# Sheet1.net
KiCad netlist of a schematic drawn in Altium Designer
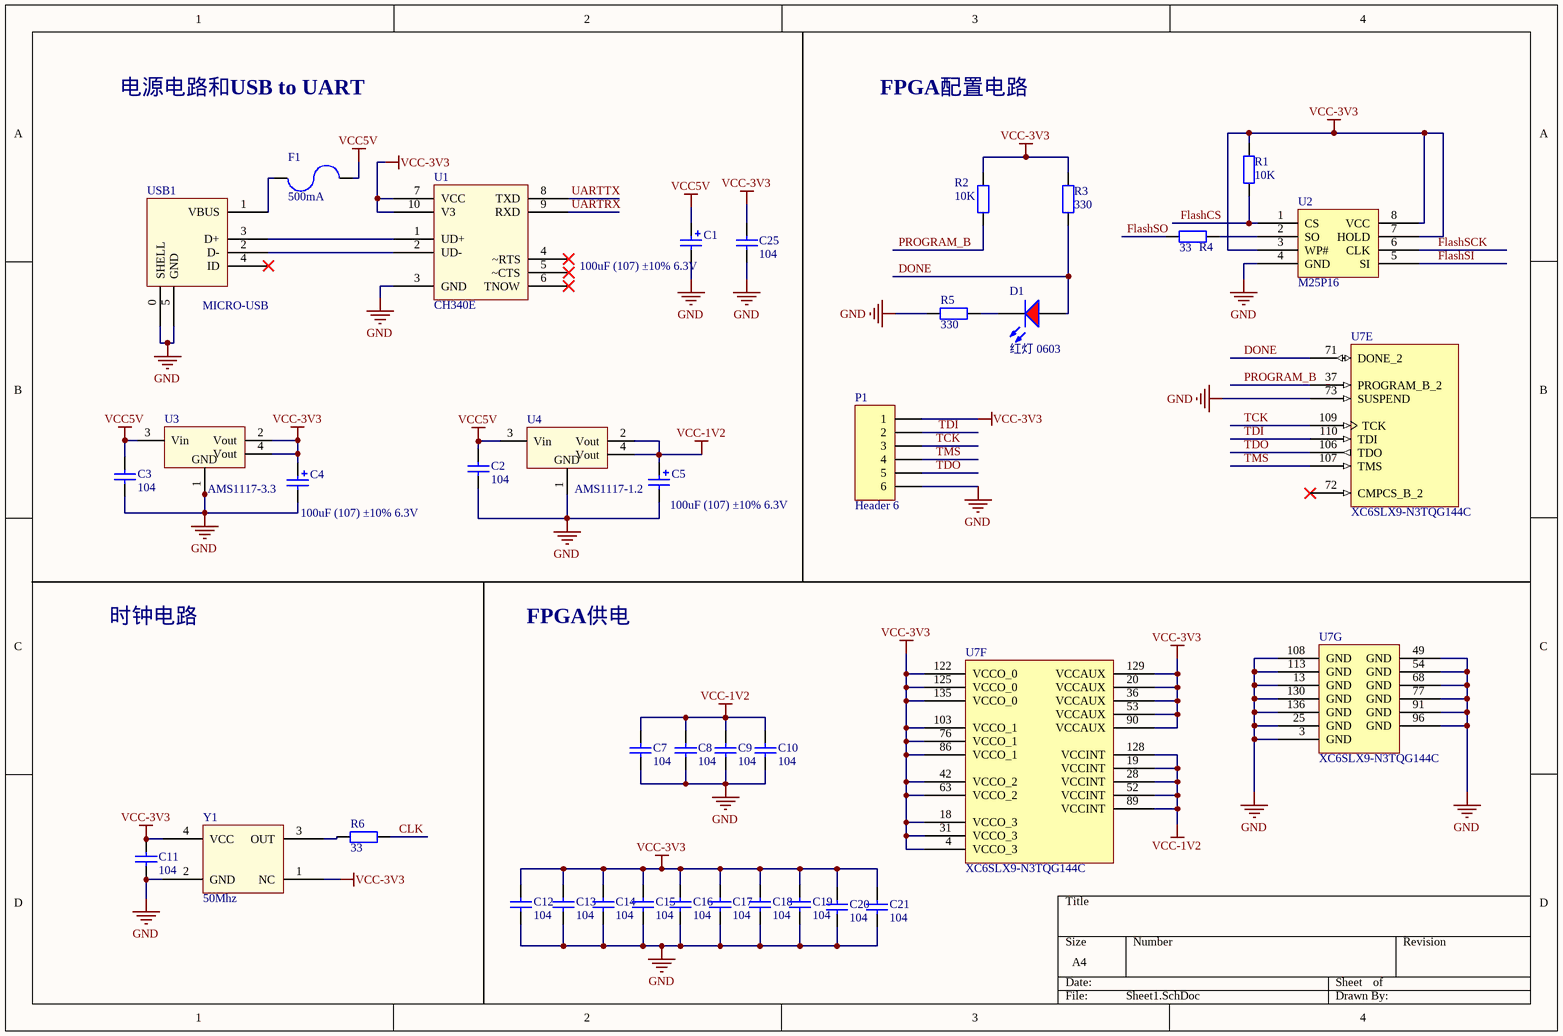
[diagram p0: Sheet1.SchDoc]

(export (version "E")
  (design (tool "Eeschema 10.0.6"))
  (components
    (comp (ref "C1")
      (value "100uF (107) ±10% 6.3V")
      (footprint "CASE-B_3528")
      (description "钽电容")
      (libsource (lib "Cap") (part "3528 100uF (107) 10% 6.3V"))
    )
    (comp (ref "C2")
      (value "104")
      (footprint "0603_C")
      (description "贴片电容")
      (libsource (lib "Cap") (part "0603 30pF (300) 5% 50V"))
    )
    (comp (ref "C3")
      (value "104")
      (footprint "0603_C")
      (description "贴片电容")
      (libsource (lib "Cap") (part "0603 30pF (300) 5% 50V"))
    )
    (comp (ref "C4")
      (value "100uF (107) ±10% 6.3V")
      (footprint "CASE-B_3528")
      (description "钽电容")
      (libsource (lib "Cap") (part "3528 100uF (107) 10% 6.3V"))
    )
    (comp (ref "C5")
      (value "100uF (107) ±10% 6.3V")
      (footprint "CASE-B_3528")
      (description "钽电容")
      (libsource (lib "Cap") (part "3528 100uF (107) 10% 6.3V"))
    )
    (comp (ref "C7")
      (value "104")
      (footprint "0603_C")
      (description "贴片电容")
      (libsource (lib "Cap") (part "0603 30pF (300) 5% 50V"))
    )
    (comp (ref "C8")
      (value "104")
      (footprint "0603_C")
      (description "贴片电容")
      (libsource (lib "Cap") (part "0603 30pF (300) 5% 50V"))
    )
    (comp (ref "C9")
      (value "104")
      (footprint "0603_C")
      (description "贴片电容")
      (libsource (lib "Cap") (part "0603 30pF (300) 5% 50V"))
    )
    (comp (ref "C10")
      (value "104")
      (footprint "0603_C")
      (description "贴片电容")
      (libsource (lib "Cap") (part "0603 30pF (300) 5% 50V"))
    )
    (comp (ref "C11")
      (value "104")
      (footprint "0603_C")
      (description "贴片电容")
      (libsource (lib "Cap") (part "0603 30pF (300) 5% 50V"))
    )
    (comp (ref "C12")
      (value "104")
      (footprint "0603_C")
      (description "贴片电容")
      (libsource (lib "Cap") (part "0603 30pF (300) 5% 50V"))
    )
    (comp (ref "C13")
      (value "104")
      (footprint "0603_C")
      (description "贴片电容")
      (libsource (lib "Cap") (part "0603 30pF (300) 5% 50V"))
    )
    (comp (ref "C14")
      (value "104")
      (footprint "0603_C")
      (description "贴片电容")
      (libsource (lib "Cap") (part "0603 30pF (300) 5% 50V"))
    )
    (comp (ref "C15")
      (value "104")
      (footprint "0603_C")
      (description "贴片电容")
      (libsource (lib "Cap") (part "0603 30pF (300) 5% 50V"))
    )
    (comp (ref "C16")
      (value "104")
      (footprint "0603_C")
      (description "贴片电容")
      (libsource (lib "Cap") (part "0603 30pF (300) 5% 50V"))
    )
    (comp (ref "C17")
      (value "104")
      (footprint "0603_C")
      (description "贴片电容")
      (libsource (lib "Cap") (part "0603 30pF (300) 5% 50V"))
    )
    (comp (ref "C18")
      (value "104")
      (footprint "0603_C")
      (description "贴片电容")
      (libsource (lib "Cap") (part "0603 30pF (300) 5% 50V"))
    )
    (comp (ref "C19")
      (value "104")
      (footprint "0603_C")
      (description "贴片电容")
      (libsource (lib "Cap") (part "0603 30pF (300) 5% 50V"))
    )
    (comp (ref "C20")
      (value "104")
      (footprint "0603_C")
      (description "贴片电容")
      (libsource (lib "Cap") (part "0603 30pF (300) 5% 50V"))
    )
    (comp (ref "C21")
      (value "104")
      (footprint "0603_C")
      (description "贴片电容")
      (libsource (lib "Cap") (part "0603 30pF (300) 5% 50V"))
    )
    (comp (ref "C25")
      (value "104")
      (footprint "0603_C")
      (description "贴片电容")
      (libsource (lib "Cap") (part "0603 30pF (300) 5% 50V"))
    )
    (comp (ref "D1")
      (value "红灯 0603")
      (footprint "0603_LED_S1")
      (description "发光二极管")
      (libsource (lib "LED") (part "0603 红灯"))
    )
    (comp (ref "F1") (value "500mA") (footprint "PTC[0805]") (libsource (lib "MiniSTM32") (part "PTC")))
    (comp (ref "P1")
      (value "Header 6")
      (footprint "HDR1X6")
      (description "Header, 6-Pin")
      (fields (field (name "PUBLISHER") "Altium Limited"))
      (libsource (lib "Miscellaneous Connectors") (part "Header 6"))
    )
    (comp (ref "R1")
      (value "10K")
      (footprint "0603_R")
      (description "贴片电阻")
      (libsource (lib "") (part "0603 9.1KΩ (9101) 1%_1"))
    )
    (comp (ref "R2")
      (value "10K")
      (footprint "0603_R")
      (description "贴片电阻")
      (libsource (lib "") (part "0603 9.1KΩ (9101) 1%_1"))
    )
    (comp (ref "R3")
      (value "330")
      (footprint "0603_R")
      (description "贴片电阻")
      (libsource (lib "") (part "0603 9.1KΩ (9101) 1%_1"))
    )
    (comp (ref "R4")
      (value "33")
      (footprint "0603_R")
      (description "贴片电阻")
      (libsource (lib "RES") (part "0603 9.1KΩ (9101) 1%"))
    )
    (comp (ref "R5")
      (value "330")
      (footprint "0603_R")
      (description "贴片电阻")
      (libsource (lib "RES") (part "0603 9.1KΩ (9101) 1%"))
    )
    (comp (ref "R6")
      (value "33")
      (footprint "0603_R")
      (description "贴片电阻")
      (libsource (lib "RES") (part "0603 9.1KΩ (9101) 1%"))
    )
    (comp (ref "U1") (value "CH340E") (footprint "MSOP10") (libsource (lib "MYDDS") (part "CH340E")))
    (comp (ref "U2") (value "M25P16") (footprint "SO-8") (libsource (lib "MiniSTM32") (part "W25Q64")))
    (comp (ref "U3")
      (value "AMS1117-3.3")
      (footprint "SOT-223(AMS1117-3.3)")
      (libsource (lib "MiniSTM32") (part "AMS1117-3.3"))
    )
    (comp (ref "U4")
      (value "AMS1117-1.2")
      (footprint "SOT-223(AMS1117-3.3)")
      (libsource (lib "MiniSTM32") (part "AMS1117-3.3"))
    )
    (comp (ref "U7")
      (value "XC6SLX9-N3TQG144C")
      (footprint "TQG144_N")
      (fields (field (name "PUBLISHER") "Altium Limited"))
      (libsource (lib "Xilinx Spartan-6") (part "XC6SLX9-N3TQG144C"))
    )
    (comp (ref "USB1")
      (value "MICRO-USB")
      (footprint "MICRO-USB")
      (libsource (lib "MYDDS") (part "MICRO-USB"))
    )
    (comp (ref "Y1") (value "50Mhz") (footprint "XTAL5032") (libsource (lib "MYSCH") (part "有源晶振")))
  )
  (nets
    (net (code "1") (name "/CLK") (class "Default")
      (node (ref "R6") (pin "1") (pinfunction "1_1") (pintype "passive"))
    )
    (net (code "2") (name "/DONE") (class "Default")
      (node (ref "D1") (pin "A") (pinfunction "A_A") (pintype "passive"))
      (node (ref "R3") (pin "1") (pinfunction "1_1") (pintype "passive"))
      (node (ref "U7") (pin "71") (pinfunction "DONE_2_71") (pintype "bidirectional"))
    )
    (net (code "3") (name "/FlashCS") (class "Default")
      (node (ref "R1") (pin "1") (pinfunction "1_1") (pintype "passive"))
      (node (ref "U2") (pin "1") (pinfunction "CS_1") (pintype "passive"))
    )
    (net (code "4") (name "/FlashSCK") (class "Default")
      (node (ref "U2") (pin "6") (pinfunction "CLK_6") (pintype "passive"))
    )
    (net (code "5") (name "/FlashSI") (class "Default")
      (node (ref "U2") (pin "5") (pinfunction "SI_5") (pintype "passive"))
    )
    (net (code "6") (name "/FlashSO") (class "Default")
      (node (ref "R4") (pin "2") (pinfunction "2_2") (pintype "passive"))
    )
    (net (code "7") (name "/PROGRAM_B") (class "Default")
      (node (ref "R2") (pin "1") (pinfunction "1_1") (pintype "passive"))
      (node (ref "U7") (pin "37") (pinfunction "PROGRAM_B_2_37") (pintype "input"))
    )
    (net (code "8") (name "/TCK") (class "Default")
      (node (ref "P1") (pin "3") (pinfunction "3_3") (pintype "passive"))
      (node (ref "U7") (pin "109") (pinfunction "TCK_109") (pintype "input"))
    )
    (net (code "9") (name "/TDI") (class "Default")
      (node (ref "P1") (pin "2") (pinfunction "2_2") (pintype "passive"))
      (node (ref "U7") (pin "110") (pinfunction "TDI_110") (pintype "input"))
    )
    (net (code "10") (name "/TDO") (class "Default")
      (node (ref "P1") (pin "5") (pinfunction "5_5") (pintype "passive"))
      (node (ref "U7") (pin "106") (pinfunction "TDO_106") (pintype "output"))
    )
    (net (code "11") (name "/TMS") (class "Default")
      (node (ref "P1") (pin "4") (pinfunction "4_4") (pintype "passive"))
      (node (ref "U7") (pin "107") (pinfunction "TMS_107") (pintype "input"))
    )
    (net (code "12") (name "/UARTRX") (class "Default")
      (node (ref "U1") (pin "9") (pinfunction "RXD_9") (pintype "passive"))
    )
    (net (code "13") (name "/UARTTX") (class "Default")
      (node (ref "U1") (pin "8") (pinfunction "TXD_8") (pintype "passive"))
    )
    (net (code "14") (name "GND") (class "Default")
      (node (ref "C1") (pin "2") (pinfunction "2_2") (pintype "passive"))
      (node (ref "C10") (pin "1") (pinfunction "1_1") (pintype "passive"))
      (node (ref "C11") (pin "1") (pinfunction "1_1") (pintype "passive"))
      (node (ref "C12") (pin "1") (pinfunction "1_1") (pintype "passive"))
      (node (ref "C13") (pin "1") (pinfunction "1_1") (pintype "passive"))
      (node (ref "C14") (pin "1") (pinfunction "1_1") (pintype "passive"))
      (node (ref "C15") (pin "1") (pinfunction "1_1") (pintype "passive"))
      (node (ref "C16") (pin "1") (pinfunction "1_1") (pintype "passive"))
      (node (ref "C17") (pin "1") (pinfunction "1_1") (pintype "passive"))
      (node (ref "C18") (pin "1") (pinfunction "1_1") (pintype "passive"))
      (node (ref "C19") (pin "1") (pinfunction "1_1") (pintype "passive"))
      (node (ref "C2") (pin "1") (pinfunction "1_1") (pintype "passive"))
      (node (ref "C20") (pin "1") (pinfunction "1_1") (pintype "passive"))
      (node (ref "C21") (pin "1") (pinfunction "1_1") (pintype "passive"))
      (node (ref "C25") (pin "1") (pinfunction "1_1") (pintype "passive"))
      (node (ref "C3") (pin "1") (pinfunction "1_1") (pintype "passive"))
      (node (ref "C4") (pin "2") (pinfunction "2_2") (pintype "passive"))
      (node (ref "C5") (pin "2") (pinfunction "2_2") (pintype "passive"))
      (node (ref "C7") (pin "1") (pinfunction "1_1") (pintype "passive"))
      (node (ref "C8") (pin "1") (pinfunction "1_1") (pintype "passive"))
      (node (ref "C9") (pin "1") (pinfunction "1_1") (pintype "passive"))
      (node (ref "P1") (pin "6") (pinfunction "6_6") (pintype "passive"))
      (node (ref "R5") (pin "2") (pinfunction "2_2") (pintype "passive"))
      (node (ref "U1") (pin "3") (pinfunction "GND_3") (pintype "passive"))
      (node (ref "U2") (pin "4") (pinfunction "GND_4") (pintype "passive"))
      (node (ref "U3") (pin "1") (pinfunction "GND_1") (pintype "passive"))
      (node (ref "U4") (pin "1") (pinfunction "GND_1") (pintype "passive"))
      (node (ref "U7") (pin "108") (pinfunction "GND_108") (pintype "power_in"))
      (node (ref "U7") (pin "113") (pinfunction "GND_113") (pintype "power_in"))
      (node (ref "U7") (pin "13") (pinfunction "GND_13") (pintype "power_in"))
      (node (ref "U7") (pin "130") (pinfunction "GND_130") (pintype "power_in"))
      (node (ref "U7") (pin "136") (pinfunction "GND_136") (pintype "power_in"))
      (node (ref "U7") (pin "25") (pinfunction "GND_25") (pintype "power_in"))
      (node (ref "U7") (pin "3") (pinfunction "GND_3") (pintype "power_in"))
      (node (ref "U7") (pin "49") (pinfunction "GND_49") (pintype "power_in"))
      (node (ref "U7") (pin "54") (pinfunction "GND_54") (pintype "power_in"))
      (node (ref "U7") (pin "68") (pinfunction "GND_68") (pintype "power_in"))
      (node (ref "U7") (pin "73") (pinfunction "SUSPEND_73") (pintype "input"))
      (node (ref "U7") (pin "77") (pinfunction "GND_77") (pintype "power_in"))
      (node (ref "U7") (pin "91") (pinfunction "GND_91") (pintype "power_in"))
      (node (ref "U7") (pin "96") (pinfunction "GND_96") (pintype "power_in"))
      (node (ref "USB1") (pin "0") (pinfunction "SHELL_0") (pintype "passive"))
      (node (ref "USB1") (pin "5") (pinfunction "GND_5") (pintype "passive"))
      (node (ref "Y1") (pin "2") (pinfunction "GND_2") (pintype "passive"))
    )
    (net (code "15") (name "Net-(D1-PadK)") (class "Default")
      (node (ref "D1") (pin "K") (pinfunction "K_K") (pintype "passive"))
      (node (ref "R5") (pin "1") (pinfunction "1_1") (pintype "passive"))
    )
    (net (code "16") (name "Net-(U1-UD+)") (class "Default")
      (node (ref "U1") (pin "1") (pinfunction "UD+_1") (pintype "passive"))
      (node (ref "USB1") (pin "3") (pinfunction "D+_3") (pintype "passive"))
    )
    (net (code "17") (name "Net-(U1-UD-)") (class "Default")
      (node (ref "U1") (pin "2") (pinfunction "UD-_2") (pintype "passive"))
      (node (ref "USB1") (pin "2") (pinfunction "D-_2") (pintype "passive"))
    )
    (net (code "18") (name "Net-(U2-SO)") (class "Default")
      (node (ref "R4") (pin "1") (pinfunction "1_1") (pintype "passive"))
      (node (ref "U2") (pin "2") (pinfunction "SO_2") (pintype "passive"))
    )
    (net (code "19") (name "Net-(USB1-VBUS)") (class "Default")
      (node (ref "F1") (pin "2") (pinfunction "2_2") (pintype "passive"))
      (node (ref "USB1") (pin "1") (pinfunction "VBUS_1") (pintype "passive"))
    )
    (net (code "20") (name "Net-(Y1-OUT)") (class "Default")
      (node (ref "R6") (pin "2") (pinfunction "2_2") (pintype "passive"))
      (node (ref "Y1") (pin "3") (pinfunction "OUT_3") (pintype "passive"))
    )
    (net (code "21") (name "VCC-1V2") (class "Default")
      (node (ref "C10") (pin "2") (pinfunction "2_2") (pintype "passive"))
      (node (ref "C5") (pin "1") (pinfunction "1_1") (pintype "passive"))
      (node (ref "C7") (pin "2") (pinfunction "2_2") (pintype "passive"))
      (node (ref "C8") (pin "2") (pinfunction "2_2") (pintype "passive"))
      (node (ref "C9") (pin "2") (pinfunction "2_2") (pintype "passive"))
      (node (ref "U4") (pin "2") (pinfunction "Vout_2") (pintype "passive"))
      (node (ref "U4") (pin "4") (pinfunction "Vout_4") (pintype "passive"))
      (node (ref "U7") (pin "128") (pinfunction "VCCINT_128") (pintype "power_in"))
      (node (ref "U7") (pin "19") (pinfunction "VCCINT_19") (pintype "power_in"))
      (node (ref "U7") (pin "28") (pinfunction "VCCINT_28") (pintype "power_in"))
      (node (ref "U7") (pin "52") (pinfunction "VCCINT_52") (pintype "power_in"))
      (node (ref "U7") (pin "89") (pinfunction "VCCINT_89") (pintype "power_in"))
    )
    (net (code "22") (name "VCC-3V3") (class "Default")
      (node (ref "C11") (pin "2") (pinfunction "2_2") (pintype "passive"))
      (node (ref "C12") (pin "2") (pinfunction "2_2") (pintype "passive"))
      (node (ref "C13") (pin "2") (pinfunction "2_2") (pintype "passive"))
      (node (ref "C14") (pin "2") (pinfunction "2_2") (pintype "passive"))
      (node (ref "C15") (pin "2") (pinfunction "2_2") (pintype "passive"))
      (node (ref "C16") (pin "2") (pinfunction "2_2") (pintype "passive"))
      (node (ref "C17") (pin "2") (pinfunction "2_2") (pintype "passive"))
      (node (ref "C18") (pin "2") (pinfunction "2_2") (pintype "passive"))
      (node (ref "C19") (pin "2") (pinfunction "2_2") (pintype "passive"))
      (node (ref "C20") (pin "2") (pinfunction "2_2") (pintype "passive"))
      (node (ref "C21") (pin "2") (pinfunction "2_2") (pintype "passive"))
      (node (ref "C25") (pin "2") (pinfunction "2_2") (pintype "passive"))
      (node (ref "C4") (pin "1") (pinfunction "1_1") (pintype "passive"))
      (node (ref "P1") (pin "1") (pinfunction "1_1") (pintype "passive"))
      (node (ref "R1") (pin "2") (pinfunction "2_2") (pintype "passive"))
      (node (ref "R2") (pin "2") (pinfunction "2_2") (pintype "passive"))
      (node (ref "R3") (pin "2") (pinfunction "2_2") (pintype "passive"))
      (node (ref "U1") (pin "10") (pinfunction "V3_10") (pintype "passive"))
      (node (ref "U1") (pin "7") (pinfunction "VCC_7") (pintype "passive"))
      (node (ref "U2") (pin "3") (pinfunction "WP#_3") (pintype "passive"))
      (node (ref "U2") (pin "7") (pinfunction "HOLD_7") (pintype "passive"))
      (node (ref "U2") (pin "8") (pinfunction "VCC_8") (pintype "passive"))
      (node (ref "U3") (pin "2") (pinfunction "Vout_2") (pintype "passive"))
      (node (ref "U3") (pin "4") (pinfunction "Vout_4") (pintype "passive"))
      (node (ref "U7") (pin "103") (pinfunction "VCCO_1_103") (pintype "power_in"))
      (node (ref "U7") (pin "122") (pinfunction "VCCO_0_122") (pintype "power_in"))
      (node (ref "U7") (pin "125") (pinfunction "VCCO_0_125") (pintype "power_in"))
      (node (ref "U7") (pin "129") (pinfunction "VCCAUX_129") (pintype "power_in"))
      (node (ref "U7") (pin "135") (pinfunction "VCCO_0_135") (pintype "power_in"))
      (node (ref "U7") (pin "18") (pinfunction "VCCO_3_18") (pintype "power_in"))
      (node (ref "U7") (pin "20") (pinfunction "VCCAUX_20") (pintype "power_in"))
      (node (ref "U7") (pin "31") (pinfunction "VCCO_3_31") (pintype "power_in"))
      (node (ref "U7") (pin "36") (pinfunction "VCCAUX_36") (pintype "power_in"))
      (node (ref "U7") (pin "4") (pinfunction "VCCO_3_4") (pintype "power_in"))
      (node (ref "U7") (pin "42") (pinfunction "VCCO_2_42") (pintype "power_in"))
      (node (ref "U7") (pin "53") (pinfunction "VCCAUX_53") (pintype "power_in"))
      (node (ref "U7") (pin "63") (pinfunction "VCCO_2_63") (pintype "power_in"))
      (node (ref "U7") (pin "76") (pinfunction "VCCO_1_76") (pintype "power_in"))
      (node (ref "U7") (pin "86") (pinfunction "VCCO_1_86") (pintype "power_in"))
      (node (ref "U7") (pin "90") (pinfunction "VCCAUX_90") (pintype "power_in"))
      (node (ref "Y1") (pin "1") (pinfunction "NC_1") (pintype "passive"))
      (node (ref "Y1") (pin "4") (pinfunction "VCC_4") (pintype "passive"))
    )
    (net (code "23") (name "VCC5V") (class "Default")
      (node (ref "C1") (pin "1") (pinfunction "1_1") (pintype "passive"))
      (node (ref "C2") (pin "2") (pinfunction "2_2") (pintype "passive"))
      (node (ref "C3") (pin "2") (pinfunction "2_2") (pintype "passive"))
      (node (ref "F1") (pin "1") (pinfunction "1_1") (pintype "passive"))
      (node (ref "U3") (pin "3") (pinfunction "Vin_3") (pintype "passive"))
      (node (ref "U4") (pin "3") (pinfunction "Vin_3") (pintype "passive"))
    )
    (net (code "24") (name "unconnected-(U1-TNOW-Pad6)") (class "Default")
      (node (ref "U1") (pin "6") (pinfunction "TNOW_6") (pintype "passive+no_connect"))
    )
    (net (code "25") (name "unconnected-(U1-~CTS-Pad5)") (class "Default")
      (node (ref "U1") (pin "5") (pinfunction "~CTS_5") (pintype "passive+no_connect"))
    )
    (net (code "26") (name "unconnected-(U1-~RTS-Pad4)") (class "Default")
      (node (ref "U1") (pin "4") (pinfunction "~RTS_4") (pintype "passive+no_connect"))
    )
    (net (code "27") (name "unconnected-(U7E-CMPCS_B_2-Pad72)") (class "Default")
      (node (ref "U7") (pin "72") (pinfunction "CMPCS_B_2_72") (pintype "input+no_connect"))
    )
    (net (code "28") (name "unconnected-(USB1-ID-Pad4)") (class "Default")
      (node (ref "USB1") (pin "4") (pinfunction "ID_4") (pintype "passive+no_connect"))
    )
  )
)
